# 20_-_ETHERNET_SATA.net
KiCad netlist of a schematic drawn in Altium Designer
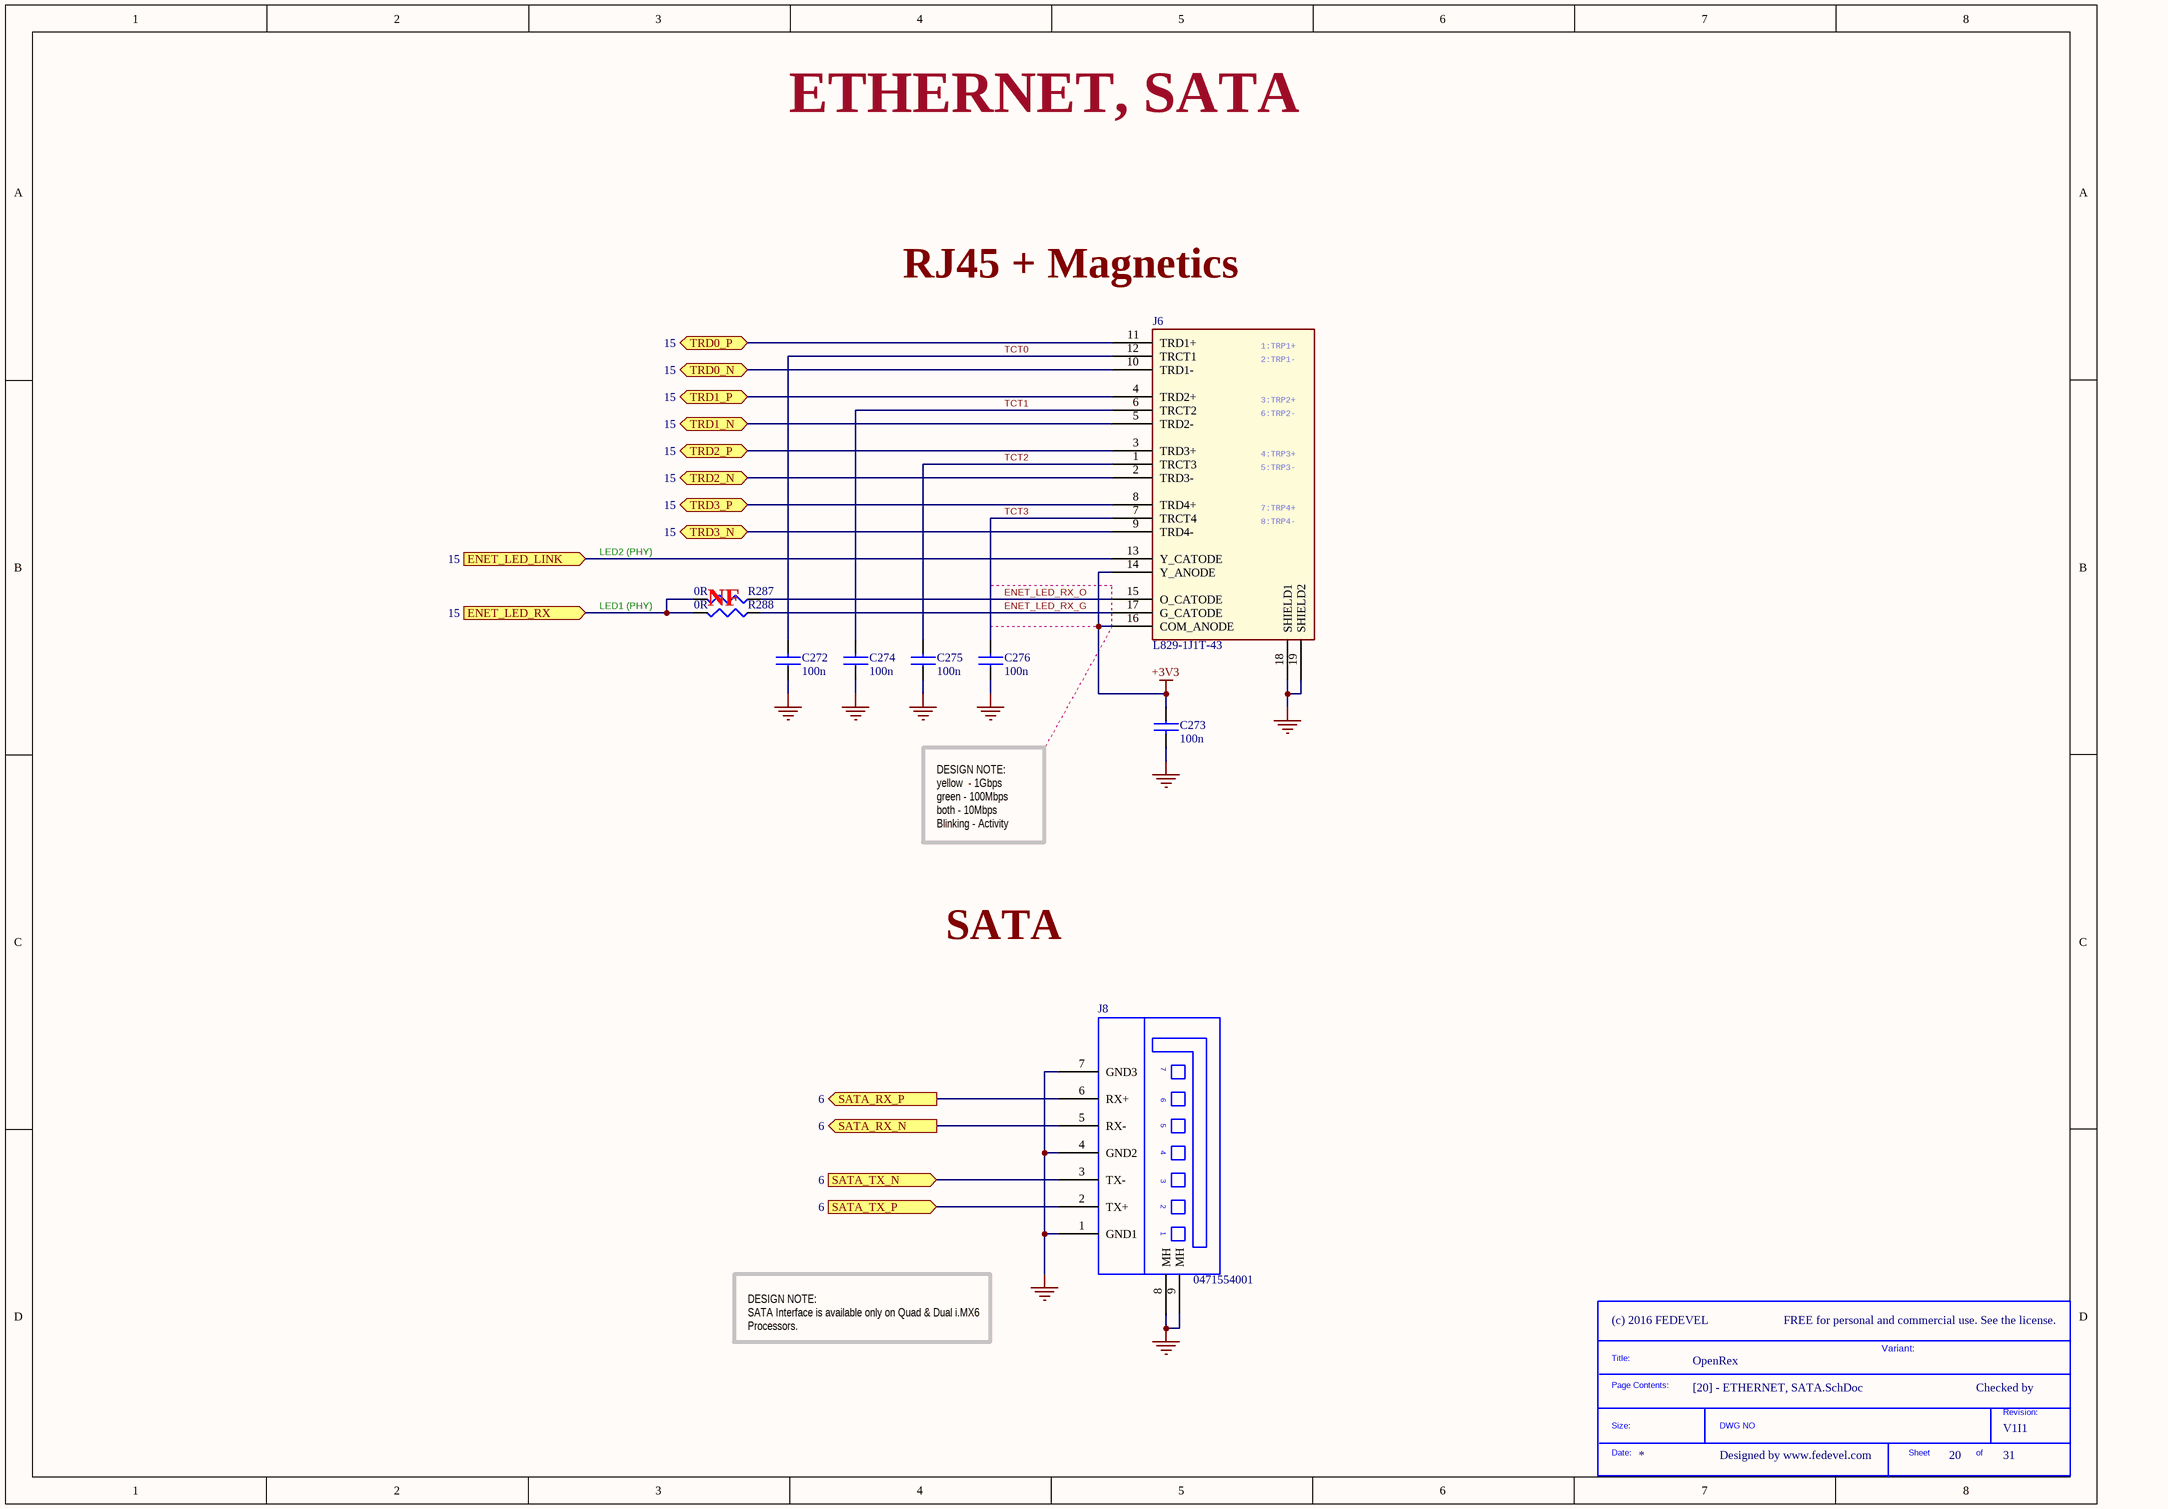
[diagram p0: [20] - ETHERNET, SATA.SchDoc]

(export (version "E")
  (design (tool "Eeschema 10.0.6"))
  (components
    (comp (ref "C272")
      (value "100n")
      (footprint "C0402")
      (description "CAP CER .10UF 50V X5R 10% 0402")
      (fields
        (field (name "MANUFACTURER") "TDK Corporation")
        (field (name "MANUFACTURER PART NUMBER") "C1005X5R1H104K")
      )
      (libsource (lib "Integrated_Library_FEDEVEL_APR_2015") (part "C1005X5R1H104K"))
    )
    (comp (ref "C273")
      (value "100n")
      (footprint "C0402")
      (description "CAP CER .10UF 50V X5R 10% 0402")
      (fields
        (field (name "MANUFACTURER") "TDK Corporation")
        (field (name "MANUFACTURER PART NUMBER") "C1005X5R1H104K")
      )
      (libsource (lib "Integrated_Library_FEDEVEL_APR_2015") (part "C1005X5R1H104K"))
    )
    (comp (ref "C274")
      (value "100n")
      (footprint "C0402")
      (description "CAP CER .10UF 50V X5R 10% 0402")
      (fields
        (field (name "MANUFACTURER") "TDK Corporation")
        (field (name "MANUFACTURER PART NUMBER") "C1005X5R1H104K")
      )
      (libsource (lib "Integrated_Library_FEDEVEL_APR_2015") (part "C1005X5R1H104K"))
    )
    (comp (ref "C275")
      (value "100n")
      (footprint "C0402")
      (description "CAP CER .10UF 50V X5R 10% 0402")
      (fields
        (field (name "MANUFACTURER") "TDK Corporation")
        (field (name "MANUFACTURER PART NUMBER") "C1005X5R1H104K")
      )
      (libsource (lib "Integrated_Library_FEDEVEL_APR_2015") (part "C1005X5R1H104K"))
    )
    (comp (ref "C276")
      (value "100n")
      (footprint "C0402")
      (description "CAP CER .10UF 50V X5R 10% 0402")
      (fields
        (field (name "MANUFACTURER") "TDK Corporation")
        (field (name "MANUFACTURER PART NUMBER") "C1005X5R1H104K")
      )
      (libsource (lib "Integrated_Library_FEDEVEL_APR_2015") (part "C1005X5R1H104K"))
    )
    (comp (ref "J6")
      (value "L829-1J1T-43")
      (footprint "L829-1J1T-43")
      (description "CONN MAGJACK 1PORT SHLD 1000BT")
      (fields
        (field (name "MANUFACTURER") "Bel Fuse Inc")
        (field (name ".CHECKED PCB") "RF")
        (field (name ".CHECKED SCH") "RF")
      )
      (libsource (lib "Integrated_Library_FEDEVEL_APR_2015") (part "L829-1J1T-43"))
    )
    (comp (ref "J8")
      (value "0471554001")
      (footprint "SATA_VERTICAL")
      (description "CONN SATA HDR 7POS PCB VERT")
      (fields (field (name "MANUFACTURER") "Molex Inc"))
      (libsource (lib "Integrated_Library_FEDEVEL_APR_2015") (part "0471554001"))
    )
    (comp (ref "R287")
      (value "0R")
      (footprint "R0402")
      (description "RES 0.0 OHM 1/16W 0402 SMD")
      (fields
        (field (name "MANUFACTURER") "Yageo")
        (field (name "MANUFACTURER PART NUMBER") "RC0402JR-070RL")
      )
      (libsource (lib "Integrated_Library_FEDEVEL_APR_2015") (part "RC0402JR-070RL"))
    )
    (comp (ref "R288")
      (value "0R")
      (footprint "R0402")
      (description "RES 0.0 OHM 1/16W 0402 SMD")
      (fields
        (field (name "MANUFACTURER") "Yageo")
        (field (name "MANUFACTURER PART NUMBER") "RC0402JR-070RL")
      )
      (libsource (lib "Integrated_Library_FEDEVEL_APR_2015") (part "RC0402JR-070RL"))
    )
  )
  (nets
    (net (code "1") (name "+3V3") (class "Default")
      (node (ref "C273") (pin "1") (pinfunction "1_1") (pintype "passive"))
      (node (ref "J6") (pin "14") (pinfunction "Y_ANODE_14") (pintype "passive"))
      (node (ref "J6") (pin "16") (pinfunction "COM_ANODE_16") (pintype "passive"))
    )
    (net (code "2") (name "/ENET_LED_LINK") (class "Default")
      (node (ref "J6") (pin "13") (pinfunction "Y_CATODE_13") (pintype "passive"))
    )
    (net (code "3") (name "/ENET_LED_RX") (class "Default")
      (node (ref "R287") (pin "2") (pinfunction "2_2") (pintype "passive"))
      (node (ref "R288") (pin "2") (pinfunction "2_2") (pintype "passive"))
    )
    (net (code "4") (name "/ENET_LED_RX_G") (class "Default")
      (node (ref "J6") (pin "17") (pinfunction "G_CATODE_17") (pintype "passive"))
      (node (ref "R288") (pin "1") (pinfunction "1_1") (pintype "passive"))
    )
    (net (code "5") (name "/ENET_LED_RX_O") (class "Default")
      (node (ref "J6") (pin "15") (pinfunction "O_CATODE_15") (pintype "passive"))
      (node (ref "R287") (pin "1") (pinfunction "1_1") (pintype "passive"))
    )
    (net (code "6") (name "/SATA_RX_N") (class "Default")
      (node (ref "J8") (pin "5") (pinfunction "RX-_5") (pintype "passive"))
    )
    (net (code "7") (name "/SATA_RX_P") (class "Default")
      (node (ref "J8") (pin "6") (pinfunction "RX+_6") (pintype "passive"))
    )
    (net (code "8") (name "/SATA_TX_N") (class "Default")
      (node (ref "J8") (pin "3") (pinfunction "TX-_3") (pintype "passive"))
    )
    (net (code "9") (name "/SATA_TX_P") (class "Default")
      (node (ref "J8") (pin "2") (pinfunction "TX+_2") (pintype "passive"))
    )
    (net (code "10") (name "/TCT0") (class "Default")
      (node (ref "C272") (pin "2") (pinfunction "2_2") (pintype "passive"))
      (node (ref "J6") (pin "12") (pinfunction "TRCT1_12") (pintype "passive"))
    )
    (net (code "11") (name "/TCT1") (class "Default")
      (node (ref "C274") (pin "2") (pinfunction "2_2") (pintype "passive"))
      (node (ref "J6") (pin "6") (pinfunction "TRCT2_6") (pintype "passive"))
    )
    (net (code "12") (name "/TCT2") (class "Default")
      (node (ref "C275") (pin "2") (pinfunction "2_2") (pintype "passive"))
      (node (ref "J6") (pin "1") (pinfunction "TRCT3_1") (pintype "passive"))
    )
    (net (code "13") (name "/TCT3") (class "Default")
      (node (ref "C276") (pin "2") (pinfunction "2_2") (pintype "passive"))
      (node (ref "J6") (pin "7") (pinfunction "TRCT4_7") (pintype "passive"))
    )
    (net (code "14") (name "/TRD0_N") (class "Default")
      (node (ref "J6") (pin "10") (pinfunction "TRD1-_10") (pintype "passive"))
    )
    (net (code "15") (name "/TRD0_P") (class "Default")
      (node (ref "J6") (pin "11") (pinfunction "TRD1+_11") (pintype "passive"))
    )
    (net (code "16") (name "/TRD1_N") (class "Default")
      (node (ref "J6") (pin "5") (pinfunction "TRD2-_5") (pintype "passive"))
    )
    (net (code "17") (name "/TRD1_P") (class "Default")
      (node (ref "J6") (pin "4") (pinfunction "TRD2+_4") (pintype "passive"))
    )
    (net (code "18") (name "/TRD2_N") (class "Default")
      (node (ref "J6") (pin "2") (pinfunction "TRD3-_2") (pintype "passive"))
    )
    (net (code "19") (name "/TRD2_P") (class "Default")
      (node (ref "J6") (pin "3") (pinfunction "TRD3+_3") (pintype "passive"))
    )
    (net (code "20") (name "/TRD3_N") (class "Default")
      (node (ref "J6") (pin "9") (pinfunction "TRD4-_9") (pintype "passive"))
    )
    (net (code "21") (name "/TRD3_P") (class "Default")
      (node (ref "J6") (pin "8") (pinfunction "TRD4+_8") (pintype "passive"))
    )
    (net (code "22") (name "GND") (class "Default")
      (node (ref "C272") (pin "1") (pinfunction "1_1") (pintype "passive"))
      (node (ref "C273") (pin "2") (pinfunction "2_2") (pintype "passive"))
      (node (ref "C274") (pin "1") (pinfunction "1_1") (pintype "passive"))
      (node (ref "C275") (pin "1") (pinfunction "1_1") (pintype "passive"))
      (node (ref "C276") (pin "1") (pinfunction "1_1") (pintype "passive"))
      (node (ref "J6") (pin "18") (pinfunction "SHIELD1_18") (pintype "passive"))
      (node (ref "J6") (pin "19") (pinfunction "SHIELD2_19") (pintype "passive"))
      (node (ref "J8") (pin "1") (pinfunction "GND1_1") (pintype "passive"))
      (node (ref "J8") (pin "4") (pinfunction "GND2_4") (pintype "passive"))
      (node (ref "J8") (pin "7") (pinfunction "GND3_7") (pintype "passive"))
      (node (ref "J8") (pin "8") (pinfunction "MH_8") (pintype "passive"))
      (node (ref "J8") (pin "9") (pinfunction "MH_9") (pintype "passive"))
    )
  )
)
